# power_sub.net
KiCad netlist of a schematic drawn in EAGLE
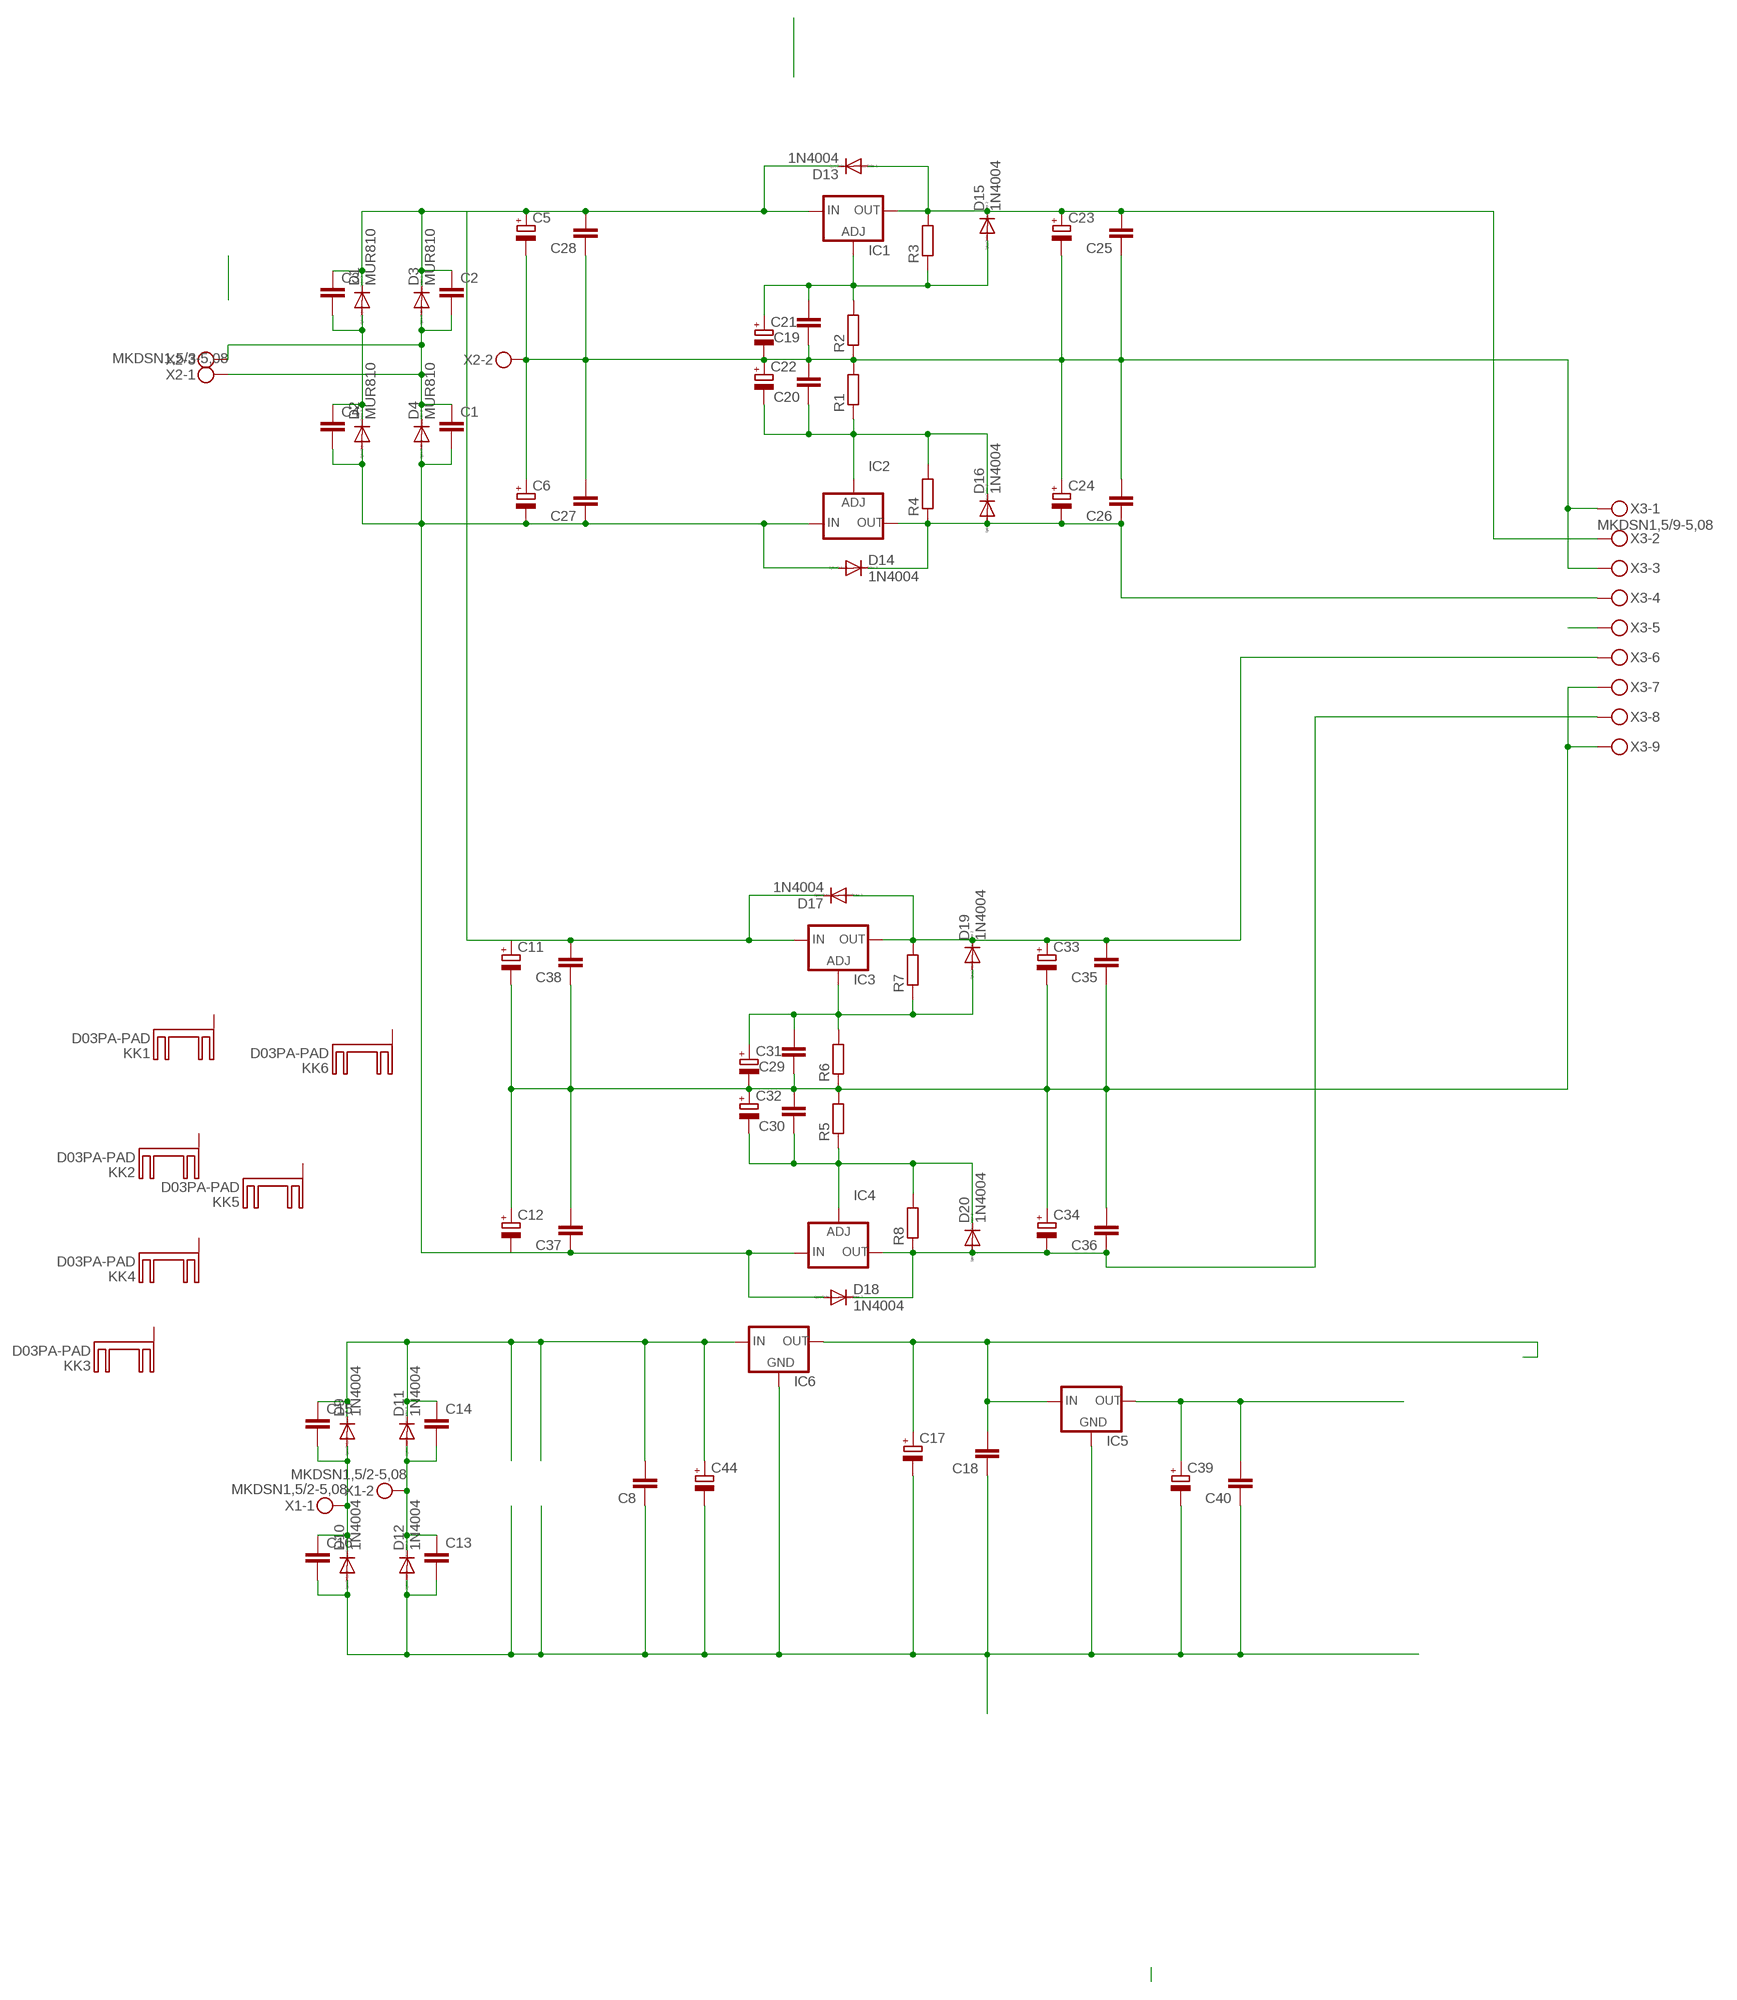
[diagram p0: schematic, sheet 1]

(export (version "E")
  (design (tool "Eeschema 10.0.6"))
  (components
    (comp (ref "C1")
      (value "C-EU025-025X050")
      (footprint "eagle-import:C025-025X050")
      (libsource (lib "eagle-import") (part "C-EU025-025X050"))
    )
    (comp (ref "C2")
      (value "C-EU025-025X050")
      (footprint "eagle-import:C025-025X050")
      (libsource (lib "eagle-import") (part "C-EU025-025X050"))
    )
    (comp (ref "C3")
      (value "C-EU025-025X050")
      (footprint "eagle-import:C025-025X050")
      (libsource (lib "eagle-import") (part "C-EU025-025X050"))
    )
    (comp (ref "C4")
      (value "C-EU025-025X050")
      (footprint "eagle-import:C025-025X050")
      (libsource (lib "eagle-import") (part "C-EU025-025X050"))
    )
    (comp (ref "C5")
      (value "CPOL-EUE7.5-18")
      (footprint "eagle-import:E7,5-18")
      (libsource (lib "eagle-import") (part "CPOL-EUE7.5-18"))
    )
    (comp (ref "C6")
      (value "CPOL-EUE7.5-18")
      (footprint "eagle-import:E7,5-18")
      (libsource (lib "eagle-import") (part "CPOL-EUE7.5-18"))
    )
    (comp (ref "C8")
      (value "C-EU050-045X075")
      (footprint "eagle-import:C050-045X075")
      (libsource (lib "eagle-import") (part "C-EU050-045X075"))
    )
    (comp (ref "C11")
      (value "CPOL-EUE7.5-18")
      (footprint "eagle-import:E7,5-18")
      (libsource (lib "eagle-import") (part "CPOL-EUE7.5-18"))
    )
    (comp (ref "C12")
      (value "CPOL-EUE7.5-18")
      (footprint "eagle-import:E7,5-18")
      (libsource (lib "eagle-import") (part "CPOL-EUE7.5-18"))
    )
    (comp (ref "C13")
      (value "C-EU025-025X050")
      (footprint "eagle-import:C025-025X050")
      (libsource (lib "eagle-import") (part "C-EU025-025X050"))
    )
    (comp (ref "C14")
      (value "C-EU025-025X050")
      (footprint "eagle-import:C025-025X050")
      (libsource (lib "eagle-import") (part "C-EU025-025X050"))
    )
    (comp (ref "C15")
      (value "C-EU025-025X050")
      (footprint "eagle-import:C025-025X050")
      (libsource (lib "eagle-import") (part "C-EU025-025X050"))
    )
    (comp (ref "C16")
      (value "C-EU025-025X050")
      (footprint "eagle-import:C025-025X050")
      (libsource (lib "eagle-import") (part "C-EU025-025X050"))
    )
    (comp (ref "C17")
      (value "CPOL-EUE5-10.5")
      (footprint "eagle-import:E5-10,5")
      (libsource (lib "eagle-import") (part "CPOL-EUE5-10.5"))
    )
    (comp (ref "C18")
      (value "C-EU050-045X075")
      (footprint "eagle-import:C050-045X075")
      (libsource (lib "eagle-import") (part "C-EU050-045X075"))
    )
    (comp (ref "C19")
      (value "C-EU050-045X075")
      (footprint "eagle-import:C050-045X075")
      (libsource (lib "eagle-import") (part "C-EU050-045X075"))
    )
    (comp (ref "C20")
      (value "C-EU050-045X075")
      (footprint "eagle-import:C050-045X075")
      (libsource (lib "eagle-import") (part "C-EU050-045X075"))
    )
    (comp (ref "C21")
      (value "CPOL-EUE5-8.5")
      (footprint "eagle-import:E5-8,5")
      (libsource (lib "eagle-import") (part "CPOL-EUE5-8.5"))
    )
    (comp (ref "C22")
      (value "CPOL-EUE5-8.5")
      (footprint "eagle-import:E5-8,5")
      (libsource (lib "eagle-import") (part "CPOL-EUE5-8.5"))
    )
    (comp (ref "C23")
      (value "CPOL-EUE5-10.5")
      (footprint "eagle-import:E5-10,5")
      (libsource (lib "eagle-import") (part "CPOL-EUE5-10.5"))
    )
    (comp (ref "C24")
      (value "CPOL-EUE5-10.5")
      (footprint "eagle-import:E5-10,5")
      (libsource (lib "eagle-import") (part "CPOL-EUE5-10.5"))
    )
    (comp (ref "C25")
      (value "C-EU050-045X075")
      (footprint "eagle-import:C050-045X075")
      (libsource (lib "eagle-import") (part "C-EU050-045X075"))
    )
    (comp (ref "C26")
      (value "C-EU050-045X075")
      (footprint "eagle-import:C050-045X075")
      (libsource (lib "eagle-import") (part "C-EU050-045X075"))
    )
    (comp (ref "C27")
      (value "C-EU050-045X075")
      (footprint "eagle-import:C050-045X075")
      (libsource (lib "eagle-import") (part "C-EU050-045X075"))
    )
    (comp (ref "C28")
      (value "C-EU050-045X075")
      (footprint "eagle-import:C050-045X075")
      (libsource (lib "eagle-import") (part "C-EU050-045X075"))
    )
    (comp (ref "C29")
      (value "C-EU050-045X075")
      (footprint "eagle-import:C050-045X075")
      (libsource (lib "eagle-import") (part "C-EU050-045X075"))
    )
    (comp (ref "C30")
      (value "C-EU050-045X075")
      (footprint "eagle-import:C050-045X075")
      (libsource (lib "eagle-import") (part "C-EU050-045X075"))
    )
    (comp (ref "C31")
      (value "CPOL-EUE5-8.5")
      (footprint "eagle-import:E5-8,5")
      (libsource (lib "eagle-import") (part "CPOL-EUE5-8.5"))
    )
    (comp (ref "C32")
      (value "CPOL-EUE5-8.5")
      (footprint "eagle-import:E5-8,5")
      (libsource (lib "eagle-import") (part "CPOL-EUE5-8.5"))
    )
    (comp (ref "C33")
      (value "CPOL-EUE5-10.5")
      (footprint "eagle-import:E5-10,5")
      (libsource (lib "eagle-import") (part "CPOL-EUE5-10.5"))
    )
    (comp (ref "C34")
      (value "CPOL-EUE5-10.5")
      (footprint "eagle-import:E5-10,5")
      (libsource (lib "eagle-import") (part "CPOL-EUE5-10.5"))
    )
    (comp (ref "C35")
      (value "C-EU050-045X075")
      (footprint "eagle-import:C050-045X075")
      (libsource (lib "eagle-import") (part "C-EU050-045X075"))
    )
    (comp (ref "C36")
      (value "C-EU050-045X075")
      (footprint "eagle-import:C050-045X075")
      (libsource (lib "eagle-import") (part "C-EU050-045X075"))
    )
    (comp (ref "C37")
      (value "C-EU050-045X075")
      (footprint "eagle-import:C050-045X075")
      (libsource (lib "eagle-import") (part "C-EU050-045X075"))
    )
    (comp (ref "C38")
      (value "C-EU050-045X075")
      (footprint "eagle-import:C050-045X075")
      (libsource (lib "eagle-import") (part "C-EU050-045X075"))
    )
    (comp (ref "C39")
      (value "CPOL-EUE5-10.5")
      (footprint "eagle-import:E5-10,5")
      (libsource (lib "eagle-import") (part "CPOL-EUE5-10.5"))
    )
    (comp (ref "C40")
      (value "C-EU050-045X075")
      (footprint "eagle-import:C050-045X075")
      (libsource (lib "eagle-import") (part "C-EU050-045X075"))
    )
    (comp (ref "C44")
      (value "CPOL-EUE7.5-18")
      (footprint "eagle-import:E7,5-18")
      (libsource (lib "eagle-import") (part "CPOL-EUE7.5-18"))
    )
    (comp (ref "D1")
      (value "MUR810")
      (footprint "eagle-import:TO220ACS")
      (libsource (lib "eagle-import") (part "MUR810"))
    )
    (comp (ref "D2")
      (value "MUR810")
      (footprint "eagle-import:TO220ACS")
      (libsource (lib "eagle-import") (part "MUR810"))
    )
    (comp (ref "D3")
      (value "MUR810")
      (footprint "eagle-import:TO220ACS")
      (libsource (lib "eagle-import") (part "MUR810"))
    )
    (comp (ref "D4")
      (value "MUR810")
      (footprint "eagle-import:TO220ACS")
      (libsource (lib "eagle-import") (part "MUR810"))
    )
    (comp (ref "D9")
      (value "1N4004")
      (footprint "eagle-import:DO41-10")
      (libsource (lib "eagle-import") (part "1N4004"))
    )
    (comp (ref "D10")
      (value "1N4004")
      (footprint "eagle-import:DO41-10")
      (libsource (lib "eagle-import") (part "1N4004"))
    )
    (comp (ref "D11")
      (value "1N4004")
      (footprint "eagle-import:DO41-10")
      (libsource (lib "eagle-import") (part "1N4004"))
    )
    (comp (ref "D12")
      (value "1N4004")
      (footprint "eagle-import:DO41-10")
      (libsource (lib "eagle-import") (part "1N4004"))
    )
    (comp (ref "D13")
      (value "1N4004")
      (footprint "eagle-import:DO41-10")
      (libsource (lib "eagle-import") (part "1N4004"))
    )
    (comp (ref "D14")
      (value "1N4004")
      (footprint "eagle-import:DO41-10")
      (libsource (lib "eagle-import") (part "1N4004"))
    )
    (comp (ref "D15")
      (value "1N4004")
      (footprint "eagle-import:DO41-10")
      (libsource (lib "eagle-import") (part "1N4004"))
    )
    (comp (ref "D16")
      (value "1N4004")
      (footprint "eagle-import:DO41-10")
      (libsource (lib "eagle-import") (part "1N4004"))
    )
    (comp (ref "D17")
      (value "1N4004")
      (footprint "eagle-import:DO41-10")
      (libsource (lib "eagle-import") (part "1N4004"))
    )
    (comp (ref "D18")
      (value "1N4004")
      (footprint "eagle-import:DO41-10")
      (libsource (lib "eagle-import") (part "1N4004"))
    )
    (comp (ref "D19")
      (value "1N4004")
      (footprint "eagle-import:DO41-10")
      (libsource (lib "eagle-import") (part "1N4004"))
    )
    (comp (ref "D20")
      (value "1N4004")
      (footprint "eagle-import:DO41-10")
      (libsource (lib "eagle-import") (part "1N4004"))
    )
    (comp (ref "IC1")
      (value "LM317TS")
      (footprint "eagle-import:317TS")
      (libsource (lib "eagle-import") (part "LM317TS"))
    )
    (comp (ref "IC2")
      (value "LM337TS")
      (footprint "eagle-import:337TS")
      (libsource (lib "eagle-import") (part "LM337TS"))
    )
    (comp (ref "IC3")
      (value "LM317TS")
      (footprint "eagle-import:317TS")
      (libsource (lib "eagle-import") (part "LM317TS"))
    )
    (comp (ref "IC4")
      (value "LM337TS")
      (footprint "eagle-import:337TS")
      (libsource (lib "eagle-import") (part "LM337TS"))
    )
    (comp (ref "IC5")
      (value "78XXS")
      (footprint "eagle-import:78XXS")
      (libsource (lib "eagle-import") (part "78XXS"))
    )
    (comp (ref "IC6")
      (value "78XXS")
      (footprint "eagle-import:78XXS")
      (libsource (lib "eagle-import") (part "78XXS"))
    )
    (comp (ref "KK1")
      (value "D03PA-PAD")
      (footprint "eagle-import:D03PA-PAD")
      (libsource (lib "eagle-import") (part "D03PA-PAD"))
    )
    (comp (ref "KK2")
      (value "D03PA-PAD")
      (footprint "eagle-import:D03PA-PAD")
      (libsource (lib "eagle-import") (part "D03PA-PAD"))
    )
    (comp (ref "KK3")
      (value "D03PA-PAD")
      (footprint "eagle-import:D03PA-PAD")
      (libsource (lib "eagle-import") (part "D03PA-PAD"))
    )
    (comp (ref "KK4")
      (value "D03PA-PAD")
      (footprint "eagle-import:D03PA-PAD")
      (libsource (lib "eagle-import") (part "D03PA-PAD"))
    )
    (comp (ref "KK5")
      (value "D03PA-PAD")
      (footprint "eagle-import:D03PA-PAD")
      (libsource (lib "eagle-import") (part "D03PA-PAD"))
    )
    (comp (ref "KK6")
      (value "D03PA-PAD")
      (footprint "eagle-import:D03PA-PAD")
      (libsource (lib "eagle-import") (part "D03PA-PAD"))
    )
    (comp (ref "R1")
      (value "R-EU_0207/12")
      (footprint "eagle-import:0207_12")
      (libsource (lib "eagle-import") (part "R-EU_0207/12"))
    )
    (comp (ref "R2")
      (value "R-EU_0207/12")
      (footprint "eagle-import:0207_12")
      (libsource (lib "eagle-import") (part "R-EU_0207/12"))
    )
    (comp (ref "R3")
      (value "R-EU_0207/12")
      (footprint "eagle-import:0207_12")
      (libsource (lib "eagle-import") (part "R-EU_0207/12"))
    )
    (comp (ref "R4")
      (value "R-EU_0207/12")
      (footprint "eagle-import:0207_12")
      (libsource (lib "eagle-import") (part "R-EU_0207/12"))
    )
    (comp (ref "R5")
      (value "R-EU_0207/12")
      (footprint "eagle-import:0207_12")
      (libsource (lib "eagle-import") (part "R-EU_0207/12"))
    )
    (comp (ref "R6")
      (value "R-EU_0207/12")
      (footprint "eagle-import:0207_12")
      (libsource (lib "eagle-import") (part "R-EU_0207/12"))
    )
    (comp (ref "R7")
      (value "R-EU_0207/12")
      (footprint "eagle-import:0207_12")
      (libsource (lib "eagle-import") (part "R-EU_0207/12"))
    )
    (comp (ref "R8")
      (value "R-EU_0207/12")
      (footprint "eagle-import:0207_12")
      (libsource (lib "eagle-import") (part "R-EU_0207/12"))
    )
    (comp (ref "X1")
      (value "MKDSN1,5/2-5,08")
      (footprint "eagle-import:MKDSN1,5_2-5,08")
      (libsource (lib "eagle-import") (part "MKDSN1,5/2-5,08"))
    )
    (comp (ref "X2")
      (value "MKDSN1,5/3-5,08")
      (footprint "eagle-import:MKDSN1,5_3-5,08")
      (libsource (lib "eagle-import") (part "MKDSN1,5/3-5,08"))
    )
    (comp (ref "X3")
      (value "MKDSN1,5/9-5,08")
      (footprint "eagle-import:MKDSN1,5_9-5,08")
      (libsource (lib "eagle-import") (part "MKDSN1,5/9-5,08"))
    )
  )
  (nets
    (net (code "1") (name "/N$17") (class "Default")
      (node (ref "C23") (pin "+") (pinfunction "+_+") (pintype "passive"))
      (node (ref "C25") (pin "2") (pinfunction "2_2") (pintype "passive"))
      (node (ref "D13") (pin "A") (pinfunction "A_A") (pintype "passive"))
      (node (ref "D15") (pin "C") (pinfunction "C_C") (pintype "passive"))
      (node (ref "IC1") (pin "2") (pinfunction "OUT_2") (pintype "passive"))
      (node (ref "R3") (pin "2") (pinfunction "2_2") (pintype "passive"))
      (node (ref "X3") (pin "2") (pinfunction "KL_2") (pintype "passive"))
    )
    (net (code "2") (name "/N$20") (class "Default")
      (node (ref "C19") (pin "2") (pinfunction "2_2") (pintype "passive"))
      (node (ref "C21") (pin "+") (pinfunction "+_+") (pintype "passive"))
      (node (ref "D15") (pin "A") (pinfunction "A_A") (pintype "passive"))
      (node (ref "IC1") (pin "1") (pinfunction "ADJ_1") (pintype "input"))
      (node (ref "R2") (pin "2") (pinfunction "2_2") (pintype "passive"))
      (node (ref "R3") (pin "1") (pinfunction "1_1") (pintype "passive"))
    )
    (net (code "3") (name "Net-(C3-Pad2)") (class "Default")
      (node (ref "C3") (pin "2") (pinfunction "2_2") (pintype "passive"))
      (node (ref "C4") (pin "1") (pinfunction "1_1") (pintype "passive"))
      (node (ref "D1") (pin "A") (pinfunction "A_A") (pintype "passive"))
      (node (ref "D2") (pin "C") (pinfunction "C_C") (pintype "passive"))
    )
    (net (code "4") (name "Net-(C13-Pad2)") (class "Default")
      (node (ref "C13") (pin "2") (pinfunction "2_2") (pintype "passive"))
      (node (ref "C16") (pin "2") (pinfunction "2_2") (pintype "passive"))
      (node (ref "C17") (pin "-") (pinfunction "-_-") (pintype "passive"))
      (node (ref "C18") (pin "1") (pinfunction "1_1") (pintype "passive"))
      (node (ref "C39") (pin "-") (pinfunction "-_-") (pintype "passive"))
      (node (ref "C40") (pin "1") (pinfunction "1_1") (pintype "passive"))
      (node (ref "C44") (pin "-") (pinfunction "-_-") (pintype "passive"))
      (node (ref "C8") (pin "1") (pinfunction "1_1") (pintype "passive"))
      (node (ref "D10") (pin "A") (pinfunction "A_A") (pintype "passive"))
      (node (ref "D12") (pin "A") (pinfunction "A_A") (pintype "passive"))
      (node (ref "IC5") (pin "GND") (pinfunction "GND_GND") (pintype "input"))
      (node (ref "IC6") (pin "GND") (pinfunction "GND_GND") (pintype "input"))
    )
    (net (code "5") (name "Net-(C14-Pad1)") (class "Default")
      (node (ref "C14") (pin "1") (pinfunction "1_1") (pintype "passive"))
      (node (ref "C15") (pin "1") (pinfunction "1_1") (pintype "passive"))
      (node (ref "C44") (pin "+") (pinfunction "+_+") (pintype "passive"))
      (node (ref "C8") (pin "2") (pinfunction "2_2") (pintype "passive"))
      (node (ref "D11") (pin "C") (pinfunction "C_C") (pintype "passive"))
      (node (ref "D9") (pin "C") (pinfunction "C_C") (pintype "passive"))
      (node (ref "IC6") (pin "IN") (pinfunction "IN_IN") (pintype "input"))
    )
    (net (code "6") (name "Net-(C17-Pad+)") (class "Default")
      (node (ref "C17") (pin "+") (pinfunction "+_+") (pintype "passive"))
      (node (ref "C18") (pin "2") (pinfunction "2_2") (pintype "passive"))
      (node (ref "IC5") (pin "IN") (pinfunction "IN_IN") (pintype "input"))
      (node (ref "IC6") (pin "OUT") (pinfunction "OUT_OUT") (pintype "passive"))
    )
    (net (code "7") (name "Net-(C39-Pad+)") (class "Default")
      (node (ref "C39") (pin "+") (pinfunction "+_+") (pintype "passive"))
      (node (ref "C40") (pin "2") (pinfunction "2_2") (pintype "passive"))
      (node (ref "IC5") (pin "OUT") (pinfunction "OUT_OUT") (pintype "passive"))
    )
    (net (code "8") (name "Net-(IC1-IN)") (class "Default")
      (node (ref "C2") (pin "1") (pinfunction "1_1") (pintype "passive"))
      (node (ref "C28") (pin "2") (pinfunction "2_2") (pintype "passive"))
      (node (ref "C3") (pin "1") (pinfunction "1_1") (pintype "passive"))
      (node (ref "C38") (pin "2") (pinfunction "2_2") (pintype "passive"))
      (node (ref "C5") (pin "+") (pinfunction "+_+") (pintype "passive"))
      (node (ref "D1") (pin "C") (pinfunction "C_C") (pintype "passive"))
      (node (ref "D13") (pin "C") (pinfunction "C_C") (pintype "passive"))
      (node (ref "D17") (pin "C") (pinfunction "C_C") (pintype "passive"))
      (node (ref "D3") (pin "C") (pinfunction "C_C") (pintype "passive"))
      (node (ref "IC1") (pin "3") (pinfunction "IN_3") (pintype "input"))
      (node (ref "IC3") (pin "3") (pinfunction "IN_3") (pintype "input"))
    )
    (net (code "9") (name "Net-(IC2-ADJ)") (class "Default")
      (node (ref "C20") (pin "1") (pinfunction "1_1") (pintype "passive"))
      (node (ref "C22") (pin "-") (pinfunction "-_-") (pintype "passive"))
      (node (ref "D16") (pin "C") (pinfunction "C_C") (pintype "passive"))
      (node (ref "IC2") (pin "1") (pinfunction "ADJ_1") (pintype "input"))
      (node (ref "R1") (pin "1") (pinfunction "1_1") (pintype "passive"))
      (node (ref "R4") (pin "2") (pinfunction "2_2") (pintype "passive"))
    )
    (net (code "10") (name "Net-(IC2-IN)") (class "Default")
      (node (ref "C1") (pin "2") (pinfunction "2_2") (pintype "passive"))
      (node (ref "C27") (pin "1") (pinfunction "1_1") (pintype "passive"))
      (node (ref "C37") (pin "1") (pinfunction "1_1") (pintype "passive"))
      (node (ref "C4") (pin "2") (pinfunction "2_2") (pintype "passive"))
      (node (ref "C6") (pin "-") (pinfunction "-_-") (pintype "passive"))
      (node (ref "D14") (pin "A") (pinfunction "A_A") (pintype "passive"))
      (node (ref "D18") (pin "A") (pinfunction "A_A") (pintype "passive"))
      (node (ref "D2") (pin "A") (pinfunction "A_A") (pintype "passive"))
      (node (ref "D4") (pin "A") (pinfunction "A_A") (pintype "passive"))
      (node (ref "IC2") (pin "2") (pinfunction "IN_2") (pintype "input"))
      (node (ref "IC4") (pin "2") (pinfunction "IN_2") (pintype "input"))
    )
    (net (code "11") (name "Net-(IC2-OUT)") (class "Default")
      (node (ref "C24") (pin "-") (pinfunction "-_-") (pintype "passive"))
      (node (ref "C26") (pin "1") (pinfunction "1_1") (pintype "passive"))
      (node (ref "D14") (pin "C") (pinfunction "C_C") (pintype "passive"))
      (node (ref "D16") (pin "A") (pinfunction "A_A") (pintype "passive"))
      (node (ref "IC2") (pin "3") (pinfunction "OUT_3") (pintype "passive"))
      (node (ref "R4") (pin "1") (pinfunction "1_1") (pintype "passive"))
      (node (ref "X3") (pin "4") (pinfunction "KL_4") (pintype "passive"))
    )
    (net (code "12") (name "Net-(IC3-ADJ)") (class "Default")
      (node (ref "C29") (pin "2") (pinfunction "2_2") (pintype "passive"))
      (node (ref "C31") (pin "+") (pinfunction "+_+") (pintype "passive"))
      (node (ref "D19") (pin "A") (pinfunction "A_A") (pintype "passive"))
      (node (ref "IC3") (pin "1") (pinfunction "ADJ_1") (pintype "input"))
      (node (ref "R6") (pin "2") (pinfunction "2_2") (pintype "passive"))
      (node (ref "R7") (pin "1") (pinfunction "1_1") (pintype "passive"))
    )
    (net (code "13") (name "Net-(IC3-OUT)") (class "Default")
      (node (ref "C33") (pin "+") (pinfunction "+_+") (pintype "passive"))
      (node (ref "C35") (pin "2") (pinfunction "2_2") (pintype "passive"))
      (node (ref "D17") (pin "A") (pinfunction "A_A") (pintype "passive"))
      (node (ref "D19") (pin "C") (pinfunction "C_C") (pintype "passive"))
      (node (ref "IC3") (pin "2") (pinfunction "OUT_2") (pintype "passive"))
      (node (ref "R7") (pin "2") (pinfunction "2_2") (pintype "passive"))
      (node (ref "X3") (pin "6") (pinfunction "KL_6") (pintype "passive"))
    )
    (net (code "14") (name "Net-(IC4-ADJ)") (class "Default")
      (node (ref "C30") (pin "1") (pinfunction "1_1") (pintype "passive"))
      (node (ref "C32") (pin "-") (pinfunction "-_-") (pintype "passive"))
      (node (ref "D20") (pin "C") (pinfunction "C_C") (pintype "passive"))
      (node (ref "IC4") (pin "1") (pinfunction "ADJ_1") (pintype "input"))
      (node (ref "R5") (pin "1") (pinfunction "1_1") (pintype "passive"))
      (node (ref "R8") (pin "2") (pinfunction "2_2") (pintype "passive"))
    )
    (net (code "15") (name "Net-(IC4-OUT)") (class "Default")
      (node (ref "C34") (pin "-") (pinfunction "-_-") (pintype "passive"))
      (node (ref "C36") (pin "1") (pinfunction "1_1") (pintype "passive"))
      (node (ref "D18") (pin "C") (pinfunction "C_C") (pintype "passive"))
      (node (ref "D20") (pin "A") (pinfunction "A_A") (pintype "passive"))
      (node (ref "IC4") (pin "3") (pinfunction "OUT_3") (pintype "passive"))
      (node (ref "R8") (pin "1") (pinfunction "1_1") (pintype "passive"))
      (node (ref "X3") (pin "8") (pinfunction "KL_8") (pintype "passive"))
    )
    (net (code "16") (name "Net-(X1A-KL)") (class "Default")
      (node (ref "C15") (pin "2") (pinfunction "2_2") (pintype "passive"))
      (node (ref "C16") (pin "1") (pinfunction "1_1") (pintype "passive"))
      (node (ref "D10") (pin "C") (pinfunction "C_C") (pintype "passive"))
      (node (ref "D9") (pin "A") (pinfunction "A_A") (pintype "passive"))
      (node (ref "X1") (pin "1") (pinfunction "KL_1") (pintype "passive"))
    )
    (net (code "17") (name "Net-(X1B-KL)") (class "Default")
      (node (ref "C13") (pin "1") (pinfunction "1_1") (pintype "passive"))
      (node (ref "C14") (pin "2") (pinfunction "2_2") (pintype "passive"))
      (node (ref "D11") (pin "A") (pinfunction "A_A") (pintype "passive"))
      (node (ref "D12") (pin "C") (pinfunction "C_C") (pintype "passive"))
      (node (ref "X1") (pin "2") (pinfunction "KL_2") (pintype "passive"))
    )
    (net (code "18") (name "Net-(X2A-KL)") (class "Default")
      (node (ref "C1") (pin "1") (pinfunction "1_1") (pintype "passive"))
      (node (ref "C2") (pin "2") (pinfunction "2_2") (pintype "passive"))
      (node (ref "D3") (pin "A") (pinfunction "A_A") (pintype "passive"))
      (node (ref "D4") (pin "C") (pinfunction "C_C") (pintype "passive"))
      (node (ref "X2") (pin "1") (pinfunction "KL_1") (pintype "passive"))
      (node (ref "X2") (pin "3") (pinfunction "KL_3") (pintype "passive"))
    )
    (net (code "19") (name "Net-(X2B-KL)") (class "Default")
      (node (ref "C19") (pin "1") (pinfunction "1_1") (pintype "passive"))
      (node (ref "C20") (pin "2") (pinfunction "2_2") (pintype "passive"))
      (node (ref "C21") (pin "-") (pinfunction "-_-") (pintype "passive"))
      (node (ref "C22") (pin "+") (pinfunction "+_+") (pintype "passive"))
      (node (ref "C23") (pin "-") (pinfunction "-_-") (pintype "passive"))
      (node (ref "C24") (pin "+") (pinfunction "+_+") (pintype "passive"))
      (node (ref "C25") (pin "1") (pinfunction "1_1") (pintype "passive"))
      (node (ref "C26") (pin "2") (pinfunction "2_2") (pintype "passive"))
      (node (ref "C27") (pin "2") (pinfunction "2_2") (pintype "passive"))
      (node (ref "C28") (pin "1") (pinfunction "1_1") (pintype "passive"))
      (node (ref "C5") (pin "-") (pinfunction "-_-") (pintype "passive"))
      (node (ref "C6") (pin "+") (pinfunction "+_+") (pintype "passive"))
      (node (ref "R1") (pin "2") (pinfunction "2_2") (pintype "passive"))
      (node (ref "R2") (pin "1") (pinfunction "1_1") (pintype "passive"))
      (node (ref "X2") (pin "2") (pinfunction "KL_2") (pintype "passive"))
      (node (ref "X3") (pin "1") (pinfunction "KL_1") (pintype "passive"))
      (node (ref "X3") (pin "3") (pinfunction "KL_3") (pintype "passive"))
    )
    (net (code "20") (name "Net-(X3G-KL)") (class "Default")
      (node (ref "C11") (pin "-") (pinfunction "-_-") (pintype "passive"))
      (node (ref "C12") (pin "+") (pinfunction "+_+") (pintype "passive"))
      (node (ref "C29") (pin "1") (pinfunction "1_1") (pintype "passive"))
      (node (ref "C30") (pin "2") (pinfunction "2_2") (pintype "passive"))
      (node (ref "C31") (pin "-") (pinfunction "-_-") (pintype "passive"))
      (node (ref "C32") (pin "+") (pinfunction "+_+") (pintype "passive"))
      (node (ref "C33") (pin "-") (pinfunction "-_-") (pintype "passive"))
      (node (ref "C34") (pin "+") (pinfunction "+_+") (pintype "passive"))
      (node (ref "C35") (pin "1") (pinfunction "1_1") (pintype "passive"))
      (node (ref "C36") (pin "2") (pinfunction "2_2") (pintype "passive"))
      (node (ref "C37") (pin "2") (pinfunction "2_2") (pintype "passive"))
      (node (ref "C38") (pin "1") (pinfunction "1_1") (pintype "passive"))
      (node (ref "R5") (pin "2") (pinfunction "2_2") (pintype "passive"))
      (node (ref "R6") (pin "1") (pinfunction "1_1") (pintype "passive"))
      (node (ref "X3") (pin "7") (pinfunction "KL_7") (pintype "passive"))
      (node (ref "X3") (pin "9") (pinfunction "KL_9") (pintype "passive"))
    )
    (net (code "21") (name "unconnected-(C11-Pad+)") (class "Default")
      (node (ref "C11") (pin "+") (pinfunction "+_+") (pintype "passive"))
    )
    (net (code "22") (name "unconnected-(C12-Pad-)") (class "Default")
      (node (ref "C12") (pin "-") (pinfunction "-_-") (pintype "passive"))
    )
    (net (code "23") (name "unconnected-(KK1-K-PadB)") (class "Default")
      (node (ref "KK1") (pin "B") (pinfunction "K_B") (pintype "passive"))
    )
    (net (code "24") (name "unconnected-(KK2-K-PadB)") (class "Default")
      (node (ref "KK2") (pin "B") (pinfunction "K_B") (pintype "passive"))
    )
    (net (code "25") (name "unconnected-(KK3-K-PadB)") (class "Default")
      (node (ref "KK3") (pin "B") (pinfunction "K_B") (pintype "passive"))
    )
    (net (code "26") (name "unconnected-(KK4-K-PadB)") (class "Default")
      (node (ref "KK4") (pin "B") (pinfunction "K_B") (pintype "passive"))
    )
    (net (code "27") (name "unconnected-(KK5-K-PadB)") (class "Default")
      (node (ref "KK5") (pin "B") (pinfunction "K_B") (pintype "passive"))
    )
    (net (code "28") (name "unconnected-(KK6-K-PadB)") (class "Default")
      (node (ref "KK6") (pin "B") (pinfunction "K_B") (pintype "passive"))
    )
    (net (code "29") (name "unconnected-(X3E-KL-Pad5)") (class "Default")
      (node (ref "X3") (pin "5") (pinfunction "KL_5") (pintype "passive"))
    )
  )
)
